# temp_sensor.net
KiCad netlist of a schematic drawn in Altium Designer
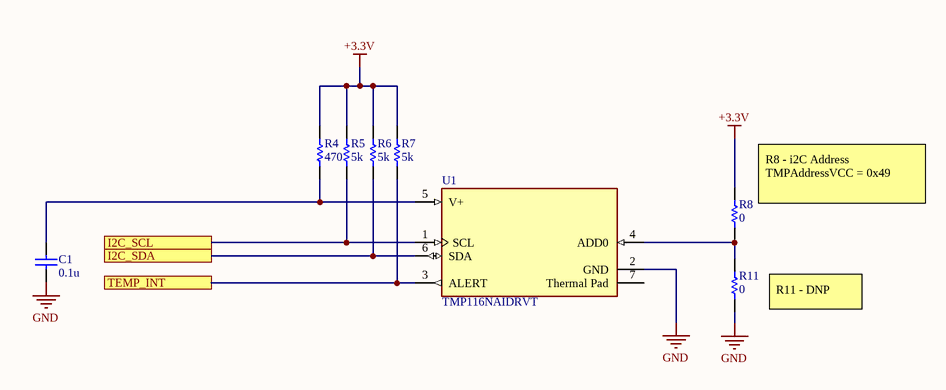
[diagram p0: temp_sensor.SchDoc]

(export (version "E")
  (design (tool "Eeschema 10.0.6"))
  (components
    (comp (ref "C1")
      (value "0.1u")
      (footprint "CAPC2013X145X50LL20T25")
      (description "C0805C104Z5VACTU")
      (fields (field (name "MANUFACTURER") "Kemet"))
      (libsource (lib "Altium Content Vault") (part "CAP"))
    )
    (comp (ref "R4")
      (value "470")
      (footprint "RESC2013X70X40LL20T20")
      (description "ERJ-6GEYJ471V")
      (fields (field (name "MANUFACTURER") "Panasonic"))
      (libsource (lib "Altium Content Vault") (part "RES"))
    )
    (comp (ref "R5")
      (value "5k")
      (footprint "RESC2013X70X40LL20T20")
      (description "2012")
      (fields (field (name "PART NUMBER") "ERJ-6GEYJ471V") (field (name "MANUFACTURER") "Panasonic"))
      (libsource (lib "Altium Content Vault") (part "RES"))
    )
    (comp (ref "R6")
      (value "5k")
      (footprint "RESC2013X70X40LL20T20")
      (description "2012")
      (fields (field (name "PART NUMBER") "ERJ-6GEYJ471V") (field (name "MANUFACTURER") "Panasonic"))
      (libsource (lib "Altium Content Vault") (part "RES"))
    )
    (comp (ref "R7")
      (value "5k")
      (footprint "RESC2013X70X40LL20T20")
      (description "2012")
      (fields (field (name "PART NUMBER") "ERJ-6GEYJ471V") (field (name "MANUFACTURER") "Panasonic"))
      (libsource (lib "Altium Content Vault") (part "RES"))
    )
    (comp (ref "R8")
      (value "0")
      (footprint "RESC2013X70X40LL20T20")
      (description "2012")
      (fields (field (name "PART NUMBER") "ERJ-6GEYJ471V") (field (name "MANUFACTURER") "Panasonic"))
      (libsource (lib "Altium Content Vault") (part "RES"))
    )
    (comp (ref "R11")
      (value "0")
      (footprint "RESC2013X70X40LL20T20")
      (description "2012")
      (fields (field (name "PART NUMBER") "ERJ-6GEYJ471V") (field (name "MANUFACTURER") "Panasonic"))
      (libsource (lib "Altium Content Vault") (part "RES"))
    )
    (comp (ref "U1")
      (value "TMP116NAIDRVT")
      (footprint "FP-DRV0006A-MFG")
      (description "SENSOR DIGITAL -55C-125C 6WSON")
      (fields
        (field (name "MANUFACTURER") "Texas Instruments")
        (field (name "OCTOPART") "https://octopart.com/tmp116naidrvt-texas+instruments-82367759")
      )
      (libsource (lib "Altium Content Vault") (part "2fad53bed00cb42ac2b52aea1ae4b02"))
    )
  )
  (nets
    (net (code "1") (name "+3.3V") (class "Default")
      (node (ref "R4") (pin "2") (pinfunction "2_2") (pintype "passive"))
      (node (ref "R5") (pin "2") (pinfunction "2_2") (pintype "passive"))
      (node (ref "R6") (pin "2") (pinfunction "2_2") (pintype "passive"))
      (node (ref "R7") (pin "2") (pinfunction "2_2") (pintype "passive"))
      (node (ref "R8") (pin "2") (pinfunction "2_2") (pintype "passive"))
    )
    (net (code "2") (name "/I2C_SCL") (class "Default")
      (node (ref "R5") (pin "1") (pinfunction "1_1") (pintype "passive"))
      (node (ref "U1") (pin "1") (pinfunction "SCL_1") (pintype "input"))
    )
    (net (code "3") (name "/I2C_SDA") (class "Default")
      (node (ref "R6") (pin "1") (pinfunction "1_1") (pintype "passive"))
      (node (ref "U1") (pin "6") (pinfunction "SDA_6") (pintype "bidirectional"))
    )
    (net (code "4") (name "/TEMP_INT") (class "Default")
      (node (ref "R7") (pin "1") (pinfunction "1_1") (pintype "passive"))
      (node (ref "U1") (pin "3") (pinfunction "ALERT_3") (pintype "output"))
    )
    (net (code "5") (name "GND") (class "Default")
      (node (ref "C1") (pin "1") (pinfunction "1_1") (pintype "passive"))
      (node (ref "R11") (pin "1") (pinfunction "1_1") (pintype "passive"))
      (node (ref "U1") (pin "2") (pinfunction "GND_2") (pintype "power_in"))
    )
    (net (code "6") (name "Net-(U1-ADD0)") (class "Default")
      (node (ref "R11") (pin "2") (pinfunction "2_2") (pintype "passive"))
      (node (ref "R8") (pin "1") (pinfunction "1_1") (pintype "passive"))
      (node (ref "U1") (pin "4") (pinfunction "ADD0_4") (pintype "input"))
    )
    (net (code "7") (name "Net-(U1-V+)") (class "Default")
      (node (ref "C1") (pin "2") (pinfunction "2_2") (pintype "passive"))
      (node (ref "R4") (pin "1") (pinfunction "1_1") (pintype "passive"))
      (node (ref "U1") (pin "5") (pinfunction "V+_5") (pintype "input"))
    )
    (net (code "8") (name "unconnected-(U1-Thermal_Pad-Pad7)") (class "Default")
      (node (ref "U1") (pin "7") (pinfunction "Thermal_Pad_7") (pintype "power_in"))
    )
  )
)
